# DigitalLevel.net
KiCad netlist of a schematic drawn in EAGLE
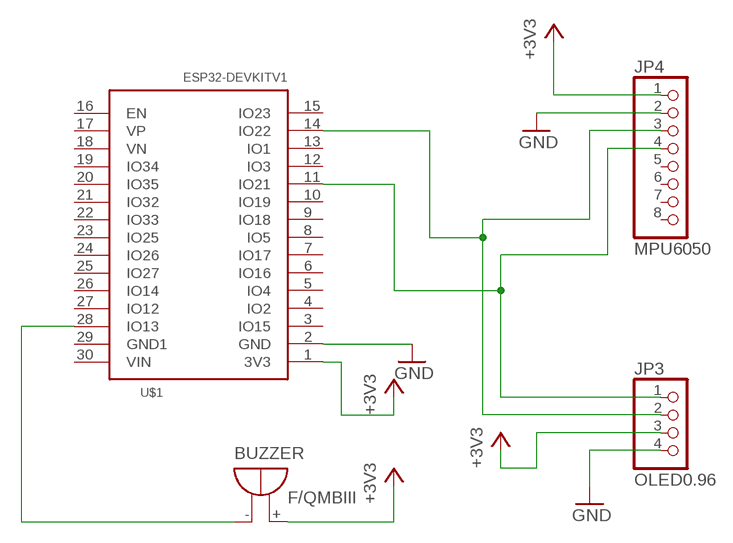
[diagram p0: schematic, sheet 1]

(export (version "E")
  (design (tool "Eeschema 10.0.6"))
  (components
    (comp (ref "BUZZER")
      (value "F/QMBIII")
      (footprint "eagle-import:F_QMBIII")
      (libsource (lib "eagle-import") (part "F/QMBIII"))
    )
    (comp (ref "JP3")
      (value "OLED0.96")
      (footprint "eagle-import:1X04")
      (libsource (lib "eagle-import") (part "PINHD-1X4"))
    )
    (comp (ref "JP4")
      (value "MPU6050")
      (footprint "eagle-import:1X08")
      (libsource (lib "eagle-import") (part "PINHD-1X8"))
    )
    (comp (ref "U$1")
      (value "ESP32DEVKITV1")
      (footprint "eagle-import:ESP32-DEVKITV1")
      (libsource (lib "eagle-import") (part "ESP32DEVKITV1"))
    )
  )
  (nets
    (net (code "1") (name "+3V3") (class "Default")
      (node (ref "BUZZER") (pin "+") (pinfunction "-_+") (pintype "passive"))
      (node (ref "JP3") (pin "3") (pinfunction "3_3") (pintype "passive"))
      (node (ref "JP4") (pin "1") (pinfunction "1_1") (pintype "passive"))
      (node (ref "U$1") (pin "1") (pinfunction "3V3_1") (pintype "bidirectional"))
    )
    (net (code "2") (name "GND") (class "Default")
      (node (ref "JP3") (pin "4") (pinfunction "4_4") (pintype "passive"))
      (node (ref "JP4") (pin "2") (pinfunction "2_2") (pintype "passive"))
      (node (ref "U$1") (pin "2") (pinfunction "GND_2") (pintype "bidirectional"))
    )
    (net (code "3") (name "Net-(BUZZER-+)") (class "Default")
      (node (ref "BUZZER") (pin "-") (pinfunction "+_-") (pintype "passive"))
      (node (ref "U$1") (pin "28") (pinfunction "IO13_28") (pintype "bidirectional"))
    )
    (net (code "4") (name "Net-(U$1-IO21)") (class "Default")
      (node (ref "JP3") (pin "1") (pinfunction "1_1") (pintype "passive"))
      (node (ref "JP4") (pin "4") (pinfunction "4_4") (pintype "passive"))
      (node (ref "U$1") (pin "11") (pinfunction "IO21_11") (pintype "bidirectional"))
    )
    (net (code "5") (name "Net-(U$1-IO22)") (class "Default")
      (node (ref "JP3") (pin "2") (pinfunction "2_2") (pintype "passive"))
      (node (ref "JP4") (pin "3") (pinfunction "3_3") (pintype "passive"))
      (node (ref "U$1") (pin "14") (pinfunction "IO22_14") (pintype "bidirectional"))
    )
    (net (code "6") (name "unconnected-(JP4-Pad5)") (class "Default")
      (node (ref "JP4") (pin "5") (pinfunction "5_5") (pintype "passive"))
    )
    (net (code "7") (name "unconnected-(JP4-Pad6)") (class "Default")
      (node (ref "JP4") (pin "6") (pinfunction "6_6") (pintype "passive"))
    )
    (net (code "8") (name "unconnected-(JP4-Pad7)") (class "Default")
      (node (ref "JP4") (pin "7") (pinfunction "7_7") (pintype "passive"))
    )
    (net (code "9") (name "unconnected-(JP4-Pad8)") (class "Default")
      (node (ref "JP4") (pin "8") (pinfunction "8_8") (pintype "passive"))
    )
    (net (code "10") (name "unconnected-(U$1-EN-Pad16)") (class "Default")
      (node (ref "U$1") (pin "16") (pinfunction "EN_16") (pintype "bidirectional"))
    )
    (net (code "11") (name "unconnected-(U$1-GND1-Pad29)") (class "Default")
      (node (ref "U$1") (pin "29") (pinfunction "GND1_29") (pintype "bidirectional"))
    )
    (net (code "12") (name "unconnected-(U$1-IO1-Pad13)") (class "Default")
      (node (ref "U$1") (pin "13") (pinfunction "IO1_13") (pintype "bidirectional"))
    )
    (net (code "13") (name "unconnected-(U$1-IO2-Pad4)") (class "Default")
      (node (ref "U$1") (pin "4") (pinfunction "IO2_4") (pintype "bidirectional"))
    )
    (net (code "14") (name "unconnected-(U$1-IO3-Pad12)") (class "Default")
      (node (ref "U$1") (pin "12") (pinfunction "IO3_12") (pintype "bidirectional"))
    )
    (net (code "15") (name "unconnected-(U$1-IO4-Pad5)") (class "Default")
      (node (ref "U$1") (pin "5") (pinfunction "IO4_5") (pintype "bidirectional"))
    )
    (net (code "16") (name "unconnected-(U$1-IO5-Pad8)") (class "Default")
      (node (ref "U$1") (pin "8") (pinfunction "IO5_8") (pintype "bidirectional"))
    )
    (net (code "17") (name "unconnected-(U$1-IO12-Pad27)") (class "Default")
      (node (ref "U$1") (pin "27") (pinfunction "IO12_27") (pintype "bidirectional"))
    )
    (net (code "18") (name "unconnected-(U$1-IO14-Pad26)") (class "Default")
      (node (ref "U$1") (pin "26") (pinfunction "IO14_26") (pintype "bidirectional"))
    )
    (net (code "19") (name "unconnected-(U$1-IO15-Pad3)") (class "Default")
      (node (ref "U$1") (pin "3") (pinfunction "IO15_3") (pintype "bidirectional"))
    )
    (net (code "20") (name "unconnected-(U$1-IO16-Pad6)") (class "Default")
      (node (ref "U$1") (pin "6") (pinfunction "IO16_6") (pintype "bidirectional"))
    )
    (net (code "21") (name "unconnected-(U$1-IO17-Pad7)") (class "Default")
      (node (ref "U$1") (pin "7") (pinfunction "IO17_7") (pintype "bidirectional"))
    )
    (net (code "22") (name "unconnected-(U$1-IO18-Pad9)") (class "Default")
      (node (ref "U$1") (pin "9") (pinfunction "IO18_9") (pintype "bidirectional"))
    )
    (net (code "23") (name "unconnected-(U$1-IO19-Pad10)") (class "Default")
      (node (ref "U$1") (pin "10") (pinfunction "IO19_10") (pintype "bidirectional"))
    )
    (net (code "24") (name "unconnected-(U$1-IO23-Pad15)") (class "Default")
      (node (ref "U$1") (pin "15") (pinfunction "IO23_15") (pintype "bidirectional"))
    )
    (net (code "25") (name "unconnected-(U$1-IO25-Pad23)") (class "Default")
      (node (ref "U$1") (pin "23") (pinfunction "IO25_23") (pintype "bidirectional"))
    )
    (net (code "26") (name "unconnected-(U$1-IO26-Pad24)") (class "Default")
      (node (ref "U$1") (pin "24") (pinfunction "IO26_24") (pintype "bidirectional"))
    )
    (net (code "27") (name "unconnected-(U$1-IO27-Pad25)") (class "Default")
      (node (ref "U$1") (pin "25") (pinfunction "IO27_25") (pintype "bidirectional"))
    )
    (net (code "28") (name "unconnected-(U$1-IO32-Pad21)") (class "Default")
      (node (ref "U$1") (pin "21") (pinfunction "IO32_21") (pintype "bidirectional"))
    )
    (net (code "29") (name "unconnected-(U$1-IO33-Pad22)") (class "Default")
      (node (ref "U$1") (pin "22") (pinfunction "IO33_22") (pintype "bidirectional"))
    )
    (net (code "30") (name "unconnected-(U$1-IO34-Pad19)") (class "Default")
      (node (ref "U$1") (pin "19") (pinfunction "IO34_19") (pintype "bidirectional"))
    )
    (net (code "31") (name "unconnected-(U$1-IO35-Pad20)") (class "Default")
      (node (ref "U$1") (pin "20") (pinfunction "IO35_20") (pintype "bidirectional"))
    )
    (net (code "32") (name "unconnected-(U$1-VIN-Pad30)") (class "Default")
      (node (ref "U$1") (pin "30") (pinfunction "VIN_30") (pintype "bidirectional"))
    )
    (net (code "33") (name "unconnected-(U$1-VN-Pad18)") (class "Default")
      (node (ref "U$1") (pin "18") (pinfunction "VN_18") (pintype "bidirectional"))
    )
    (net (code "34") (name "unconnected-(U$1-VP-Pad17)") (class "Default")
      (node (ref "U$1") (pin "17") (pinfunction "VP_17") (pintype "bidirectional"))
    )
  )
)
